# interface_dac_sma_feedback_3PS_LM317_par.net
KiCad netlist of a schematic drawn in EAGLE
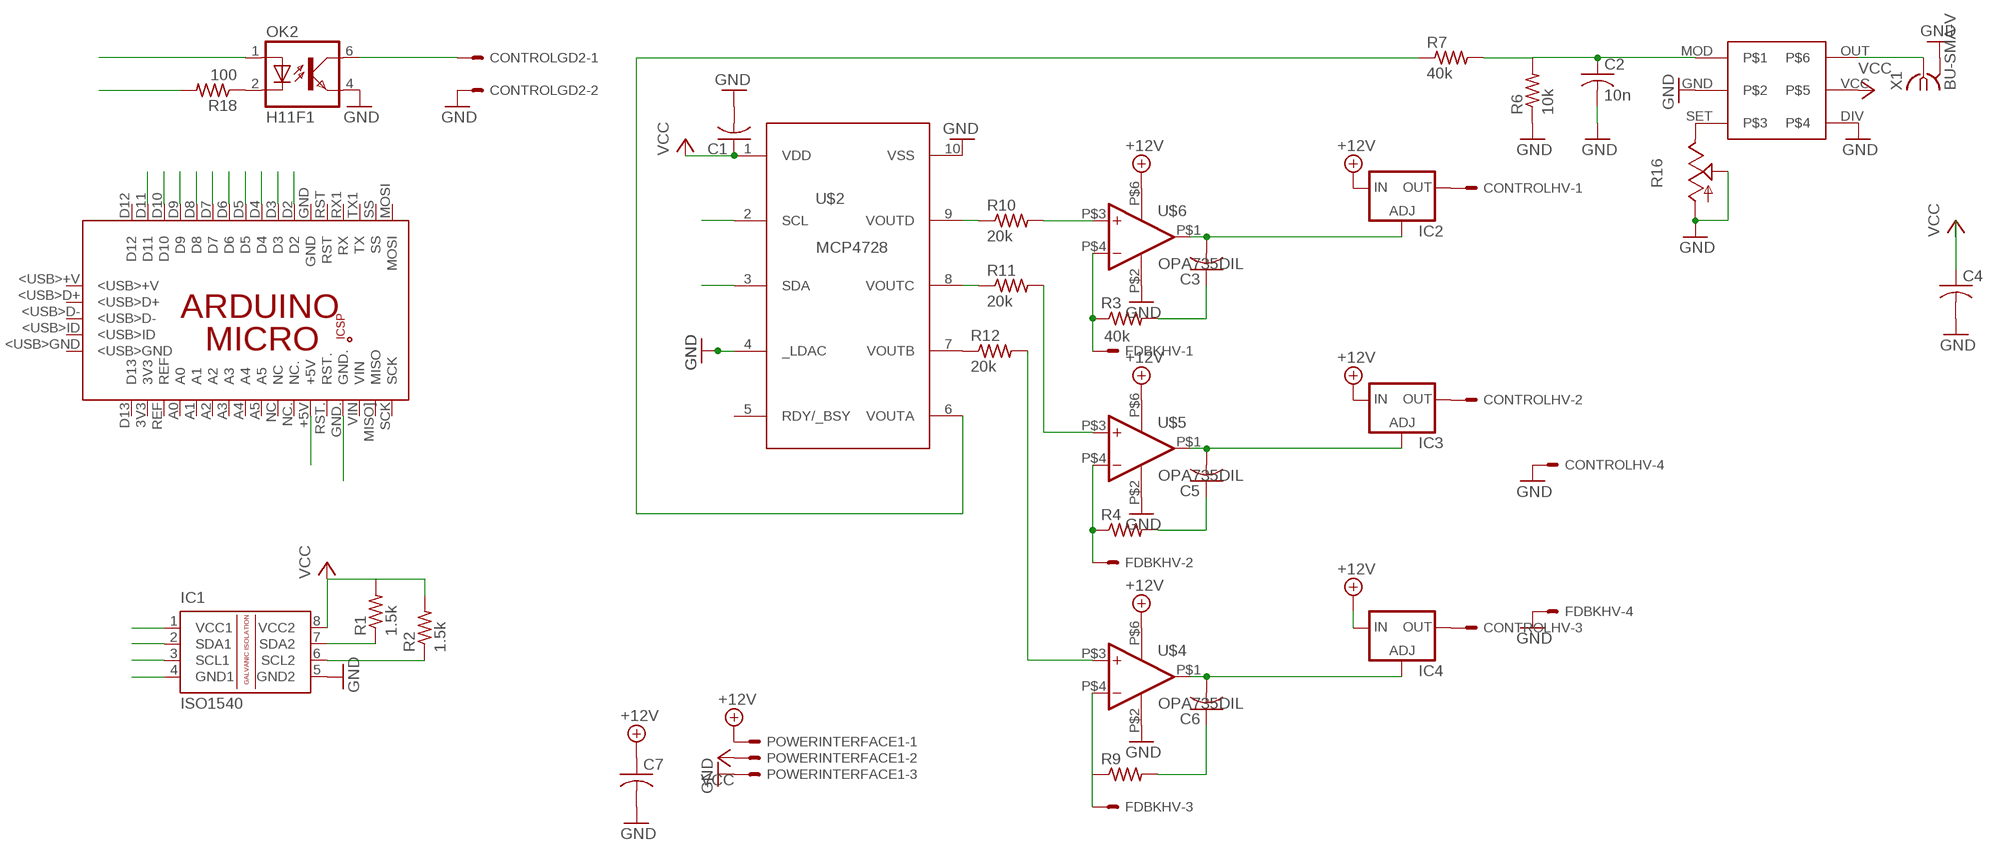
[diagram p0: schematic, sheet 1]

(export (version "E")
  (design (tool "Eeschema 10.0.6"))
  (components
    (comp (ref "C1")
      (value "C-US050-050X075")
      (footprint "eagle-import:C050-050X075")
      (libsource (lib "eagle-import") (part "C-US050-050X075"))
    )
    (comp (ref "C2")
      (value "10n")
      (footprint "eagle-import:C050-024X044")
      (libsource (lib "eagle-import") (part "resistor_C-US050-024X044"))
    )
    (comp (ref "C3")
      (value "C-US050-024X044")
      (footprint "eagle-import:C050-024X044")
      (libsource (lib "eagle-import") (part "resistor_C-US050-024X044"))
    )
    (comp (ref "C4")
      (value "C-US075-063X106")
      (footprint "eagle-import:C075-063X106")
      (libsource (lib "eagle-import") (part "resistor_C-US075-063X106"))
    )
    (comp (ref "C5")
      (value "C-US050-024X044")
      (footprint "eagle-import:C050-024X044")
      (libsource (lib "eagle-import") (part "resistor_C-US050-024X044"))
    )
    (comp (ref "C6")
      (value "C-US050-024X044")
      (footprint "eagle-import:C050-024X044")
      (libsource (lib "eagle-import") (part "resistor_C-US050-024X044"))
    )
    (comp (ref "C7")
      (value "C-US050-050X075")
      (footprint "eagle-import:C050-050X075")
      (libsource (lib "eagle-import") (part "resistor_C-US050-050X075"))
    )
    (comp (ref "CONTROLGD2")
      (value "KK-156-2")
      (footprint "eagle-import:KK-156-2")
      (libsource (lib "eagle-import") (part "KK-156-2"))
    )
    (comp (ref "CONTROLHV")
      (value "KK-156-4")
      (footprint "eagle-import:KK-156-4")
      (libsource (lib "eagle-import") (part "KK-156-4"))
    )
    (comp (ref "FDBKHV")
      (value "40k")
      (footprint "eagle-import:KK-156-4")
      (libsource (lib "eagle-import") (part "KK-156-4"))
    )
    (comp (ref "IC1")
      (value "ISO1540")
      (footprint "eagle-import:DIL08")
      (libsource (lib "eagle-import") (part "ISO1540"))
    )
    (comp (ref "IC2")
      (value "LM317TS")
      (footprint "eagle-import:317TS")
      (libsource (lib "eagle-import") (part "LM317TS"))
    )
    (comp (ref "IC3")
      (value "LM317TS")
      (footprint "eagle-import:317TS")
      (libsource (lib "eagle-import") (part "LM317TS"))
    )
    (comp (ref "IC4")
      (value "LM317TS")
      (footprint "eagle-import:317TS")
      (libsource (lib "eagle-import") (part "LM317TS"))
    )
    (comp (ref "OK2")
      (value "H11F1")
      (footprint "eagle-import:DIL05")
      (libsource (lib "eagle-import") (part "H11F1"))
    )
    (comp (ref "PCB1")
      (value "ARDUINO_MICRO")
      (footprint "eagle-import:ARDUINO_MICRO")
      (libsource (lib "eagle-import") (part "ARDUINO_MICRO"))
    )
    (comp (ref "POWERINTERFACE1")
      (value "KK-156-3")
      (footprint "eagle-import:KK-156-3")
      (libsource (lib "eagle-import") (part "KK-156-3"))
    )
    (comp (ref "R1")
      (value "1.5k")
      (footprint "eagle-import:0207_12")
      (libsource (lib "eagle-import") (part "resistor_R-US_0207/12"))
    )
    (comp (ref "R2")
      (value "1.5k")
      (footprint "eagle-import:0207_12")
      (libsource (lib "eagle-import") (part "resistor_R-US_0207/12"))
    )
    (comp (ref "R3")
      (value "R-US_0207/12")
      (footprint "eagle-import:0207_12")
      (libsource (lib "eagle-import") (part "resistor_R-US_0207/12"))
    )
    (comp (ref "R4")
      (value "R-US_0207/12")
      (footprint "eagle-import:0207_12")
      (libsource (lib "eagle-import") (part "resistor_R-US_0207/12"))
    )
    (comp (ref "R6")
      (value "10k")
      (footprint "eagle-import:0207_12")
      (libsource (lib "eagle-import") (part "resistor_R-US_0207/12"))
    )
    (comp (ref "R7")
      (value "40k")
      (footprint "eagle-import:0207_12")
      (libsource (lib "eagle-import") (part "resistor_R-US_0207/12"))
    )
    (comp (ref "R9")
      (value "R-US_0207/12")
      (footprint "eagle-import:0207_12")
      (libsource (lib "eagle-import") (part "resistor_R-US_0207/12"))
    )
    (comp (ref "R10")
      (value "20k")
      (footprint "eagle-import:0207_12")
      (libsource (lib "eagle-import") (part "resistor_R-US_0207/12"))
    )
    (comp (ref "R11")
      (value "20k")
      (footprint "eagle-import:0207_12")
      (libsource (lib "eagle-import") (part "resistor_R-US_0207/12"))
    )
    (comp (ref "R12")
      (value "20k")
      (footprint "eagle-import:0207_12")
      (libsource (lib "eagle-import") (part "resistor_R-US_0207/12"))
    )
    (comp (ref "R16")
      (value "TRIM_US-B90P")
      (footprint "eagle-import:SP19L")
      (libsource (lib "eagle-import") (part "TRIM_US-B90P"))
    )
    (comp (ref "R18")
      (value "100")
      (footprint "eagle-import:0207_12")
      (libsource (lib "eagle-import") (part "R-US_0207/12"))
    )
    (comp (ref "U$1")
      (value "LTC6992")
      (footprint "eagle-import:DIL06")
      (libsource (lib "eagle-import") (part "LTC6992"))
    )
    (comp (ref "U$2")
      (value "MCP4728DIL")
      (footprint "eagle-import:DIL10")
      (libsource (lib "eagle-import") (part "MCP4728DIL"))
    )
    (comp (ref "U$4")
      (value "OPA735DIL")
      (footprint "eagle-import:DIL6")
      (libsource (lib "eagle-import") (part "OPA735DIL"))
    )
    (comp (ref "U$5")
      (value "OPA735DIL")
      (footprint "eagle-import:DIL6")
      (libsource (lib "eagle-import") (part "OPA735DIL"))
    )
    (comp (ref "U$6")
      (value "OPA735DIL")
      (footprint "eagle-import:DIL6")
      (libsource (lib "eagle-import") (part "OPA735DIL"))
    )
    (comp (ref "X1")
      (value "BU-SMA-V")
      (footprint "eagle-import:BU-SMA-V")
      (libsource (lib "eagle-import") (part "BU-SMA-V"))
    )
  )
  (nets
    (net (code "1") (name "+12V") (class "Default")
      (node (ref "C7") (pin "1") (pinfunction "1_1") (pintype "passive"))
      (node (ref "IC2") (pin "3") (pinfunction "IN_3") (pintype "input"))
      (node (ref "IC3") (pin "3") (pinfunction "IN_3") (pintype "input"))
      (node (ref "IC4") (pin "3") (pinfunction "IN_3") (pintype "input"))
      (node (ref "POWERINTERFACE1") (pin "1") (pinfunction "S_1") (pintype "passive"))
      (node (ref "U$4") (pin "P$6") (pinfunction "V+_P$6") (pintype "power_in"))
      (node (ref "U$5") (pin "P$6") (pinfunction "V+_P$6") (pintype "power_in"))
      (node (ref "U$6") (pin "P$6") (pinfunction "V+_P$6") (pintype "power_in"))
    )
    (net (code "2") (name "/A+5") (class "Default")
      (node (ref "IC1") (pin "1") (pinfunction "VCC1_1") (pintype "input"))
      (node (ref "PCB1") (pin "+5V") (pinfunction "+5V_+5V") (pintype "bidirectional"))
    )
    (net (code "3") (name "/AGND") (class "Default")
      (node (ref "IC1") (pin "4") (pinfunction "GND1_4") (pintype "input"))
      (node (ref "PCB1") (pin "GND.") (pinfunction "GND._GND.") (pintype "bidirectional"))
      (node (ref "R18") (pin "2") (pinfunction "2_2") (pintype "passive"))
    )
    (net (code "4") (name "/N$2") (class "Default")
      (node (ref "C2") (pin "1") (pinfunction "1_1") (pintype "passive"))
      (node (ref "R6") (pin "2") (pinfunction "2_2") (pintype "passive"))
      (node (ref "R7") (pin "2") (pinfunction "2_2") (pintype "passive"))
      (node (ref "U$1") (pin "MOD") (pinfunction "P$1_MOD") (pintype "bidirectional"))
    )
    (net (code "5") (name "/PWM9") (class "Default")
      (node (ref "OK2") (pin "1") (pinfunction "A_1") (pintype "passive"))
      (node (ref "PCB1") (pin "D9") (pinfunction "D9_D9") (pintype "bidirectional"))
    )
    (net (code "6") (name "/SCL") (class "Default")
      (node (ref "IC1") (pin "3") (pinfunction "SCL1_3") (pintype "input"))
      (node (ref "PCB1") (pin "D3") (pinfunction "D3_D3") (pintype "bidirectional"))
    )
    (net (code "7") (name "/SCL_OUT") (class "Default")
      (node (ref "IC1") (pin "6") (pinfunction "SCL2_6") (pintype "input"))
      (node (ref "R2") (pin "1") (pinfunction "1_1") (pintype "passive"))
      (node (ref "U$2") (pin "2") (pinfunction "SCL_2") (pintype "bidirectional"))
    )
    (net (code "8") (name "/SDA") (class "Default")
      (node (ref "IC1") (pin "2") (pinfunction "SDA1_2") (pintype "input"))
      (node (ref "PCB1") (pin "D2") (pinfunction "D2_D2") (pintype "bidirectional"))
    )
    (net (code "9") (name "/SDA_OUT") (class "Default")
      (node (ref "IC1") (pin "7") (pinfunction "SDA2_7") (pintype "input"))
      (node (ref "R1") (pin "1") (pinfunction "1_1") (pintype "passive"))
      (node (ref "U$2") (pin "3") (pinfunction "SDA_3") (pintype "bidirectional"))
    )
    (net (code "10") (name "GND") (class "Default")
      (node (ref "C1") (pin "2") (pinfunction "2_2") (pintype "passive"))
      (node (ref "C2") (pin "2") (pinfunction "2_2") (pintype "passive"))
      (node (ref "C4") (pin "2") (pinfunction "2_2") (pintype "passive"))
      (node (ref "C7") (pin "2") (pinfunction "2_2") (pintype "passive"))
      (node (ref "CONTROLGD2") (pin "2") (pinfunction "S_2") (pintype "passive"))
      (node (ref "CONTROLHV") (pin "4") (pinfunction "S_4") (pintype "passive"))
      (node (ref "FDBKHV") (pin "4") (pinfunction "S_4") (pintype "passive"))
      (node (ref "IC1") (pin "5") (pinfunction "GND2_5") (pintype "input"))
      (node (ref "OK2") (pin "4") (pinfunction "EMIT_4") (pintype "passive"))
      (node (ref "POWERINTERFACE1") (pin "3") (pinfunction "S_3") (pintype "passive"))
      (node (ref "R16") (pin "A") (pinfunction "A_A") (pintype "passive"))
      (node (ref "R16") (pin "S") (pinfunction "S_S") (pintype "passive"))
      (node (ref "R6") (pin "1") (pinfunction "1_1") (pintype "passive"))
      (node (ref "U$1") (pin "DIV") (pinfunction "P$4_DIV") (pintype "bidirectional"))
      (node (ref "U$1") (pin "GND") (pinfunction "P$2_GND") (pintype "bidirectional"))
      (node (ref "U$2") (pin "10") (pinfunction "VSS_10") (pintype "bidirectional"))
      (node (ref "U$2") (pin "4") (pinfunction "_LDAC_4") (pintype "bidirectional"))
      (node (ref "U$4") (pin "P$2") (pinfunction "V-_P$2") (pintype "power_in"))
      (node (ref "U$5") (pin "P$2") (pinfunction "V-_P$2") (pintype "power_in"))
      (node (ref "U$6") (pin "P$2") (pinfunction "V-_P$2") (pintype "power_in"))
      (node (ref "X1") (pin "2") (pinfunction "2_2") (pintype "passive"))
      (node (ref "X1") (pin "3") (pinfunction "2_3") (pintype "passive"))
      (node (ref "X1") (pin "4") (pinfunction "2_4") (pintype "passive"))
      (node (ref "X1") (pin "5") (pinfunction "2_5") (pintype "passive"))
    )
    (net (code "11") (name "Net-(C3-Pad1)") (class "Default")
      (node (ref "C3") (pin "1") (pinfunction "1_1") (pintype "passive"))
      (node (ref "R3") (pin "2") (pinfunction "2_2") (pintype "passive"))
    )
    (net (code "12") (name "Net-(C5-Pad1)") (class "Default")
      (node (ref "C5") (pin "1") (pinfunction "1_1") (pintype "passive"))
      (node (ref "R4") (pin "2") (pinfunction "2_2") (pintype "passive"))
    )
    (net (code "13") (name "Net-(C6-Pad1)") (class "Default")
      (node (ref "C6") (pin "1") (pinfunction "1_1") (pintype "passive"))
      (node (ref "R9") (pin "2") (pinfunction "2_2") (pintype "passive"))
    )
    (net (code "14") (name "Net-(CONTROLGD2A-S)") (class "Default")
      (node (ref "CONTROLGD2") (pin "1") (pinfunction "S_1") (pintype "passive"))
      (node (ref "OK2") (pin "6") (pinfunction "COL_6") (pintype "passive"))
    )
    (net (code "15") (name "Net-(CONTROLHVA-S)") (class "Default")
      (node (ref "CONTROLHV") (pin "1") (pinfunction "S_1") (pintype "passive"))
      (node (ref "IC2") (pin "2") (pinfunction "OUT_2") (pintype "passive"))
    )
    (net (code "16") (name "Net-(CONTROLHVB-S)") (class "Default")
      (node (ref "CONTROLHV") (pin "2") (pinfunction "S_2") (pintype "passive"))
      (node (ref "IC3") (pin "2") (pinfunction "OUT_2") (pintype "passive"))
    )
    (net (code "17") (name "Net-(CONTROLHVC-S)") (class "Default")
      (node (ref "CONTROLHV") (pin "3") (pinfunction "S_3") (pintype "passive"))
      (node (ref "IC4") (pin "2") (pinfunction "OUT_2") (pintype "passive"))
    )
    (net (code "18") (name "Net-(FDBKHVA-S)") (class "Default")
      (node (ref "FDBKHV") (pin "1") (pinfunction "S_1") (pintype "passive"))
      (node (ref "R3") (pin "1") (pinfunction "1_1") (pintype "passive"))
      (node (ref "U$6") (pin "P$4") (pinfunction "-IN_P$4") (pintype "input"))
    )
    (net (code "19") (name "Net-(FDBKHVB-S)") (class "Default")
      (node (ref "FDBKHV") (pin "2") (pinfunction "S_2") (pintype "passive"))
      (node (ref "R4") (pin "1") (pinfunction "1_1") (pintype "passive"))
      (node (ref "U$5") (pin "P$4") (pinfunction "-IN_P$4") (pintype "input"))
    )
    (net (code "20") (name "Net-(FDBKHVC-S)") (class "Default")
      (node (ref "FDBKHV") (pin "3") (pinfunction "S_3") (pintype "passive"))
      (node (ref "R9") (pin "1") (pinfunction "1_1") (pintype "passive"))
      (node (ref "U$4") (pin "P$4") (pinfunction "-IN_P$4") (pintype "input"))
    )
    (net (code "21") (name "Net-(IC2-ADJ)") (class "Default")
      (node (ref "C3") (pin "2") (pinfunction "2_2") (pintype "passive"))
      (node (ref "IC2") (pin "1") (pinfunction "ADJ_1") (pintype "input"))
      (node (ref "U$6") (pin "P$1") (pinfunction "OUT_P$1") (pintype "output"))
    )
    (net (code "22") (name "Net-(IC3-ADJ)") (class "Default")
      (node (ref "C5") (pin "2") (pinfunction "2_2") (pintype "passive"))
      (node (ref "IC3") (pin "1") (pinfunction "ADJ_1") (pintype "input"))
      (node (ref "U$5") (pin "P$1") (pinfunction "OUT_P$1") (pintype "output"))
    )
    (net (code "23") (name "Net-(IC4-ADJ)") (class "Default")
      (node (ref "C6") (pin "2") (pinfunction "2_2") (pintype "passive"))
      (node (ref "IC4") (pin "1") (pinfunction "ADJ_1") (pintype "input"))
      (node (ref "U$4") (pin "P$1") (pinfunction "OUT_P$1") (pintype "output"))
    )
    (net (code "24") (name "Net-(OK2-C)") (class "Default")
      (node (ref "OK2") (pin "2") (pinfunction "C_2") (pintype "passive"))
      (node (ref "R18") (pin "1") (pinfunction "1_1") (pintype "passive"))
    )
    (net (code "25") (name "Net-(U$1-P$3)") (class "Default")
      (node (ref "R16") (pin "E") (pinfunction "E_E") (pintype "passive"))
      (node (ref "U$1") (pin "SET") (pinfunction "P$3_SET") (pintype "bidirectional"))
    )
    (net (code "26") (name "Net-(U$1-P$6)") (class "Default")
      (node (ref "U$1") (pin "OUT") (pinfunction "P$6_OUT") (pintype "bidirectional"))
      (node (ref "X1") (pin "1") (pinfunction "1_1") (pintype "passive"))
    )
    (net (code "27") (name "Net-(U$2-VOUTA)") (class "Default")
      (node (ref "R7") (pin "1") (pinfunction "1_1") (pintype "passive"))
      (node (ref "U$2") (pin "6") (pinfunction "VOUTA_6") (pintype "bidirectional"))
    )
    (net (code "28") (name "Net-(U$2-VOUTB)") (class "Default")
      (node (ref "R12") (pin "1") (pinfunction "1_1") (pintype "passive"))
      (node (ref "U$2") (pin "7") (pinfunction "VOUTB_7") (pintype "bidirectional"))
    )
    (net (code "29") (name "Net-(U$2-VOUTC)") (class "Default")
      (node (ref "R11") (pin "1") (pinfunction "1_1") (pintype "passive"))
      (node (ref "U$2") (pin "8") (pinfunction "VOUTC_8") (pintype "bidirectional"))
    )
    (net (code "30") (name "Net-(U$2-VOUTD)") (class "Default")
      (node (ref "R10") (pin "1") (pinfunction "1_1") (pintype "passive"))
      (node (ref "U$2") (pin "9") (pinfunction "VOUTD_9") (pintype "bidirectional"))
    )
    (net (code "31") (name "Net-(U$4-+IN)") (class "Default")
      (node (ref "R12") (pin "2") (pinfunction "2_2") (pintype "passive"))
      (node (ref "U$4") (pin "P$3") (pinfunction "+IN_P$3") (pintype "input"))
    )
    (net (code "32") (name "Net-(U$5-+IN)") (class "Default")
      (node (ref "R11") (pin "2") (pinfunction "2_2") (pintype "passive"))
      (node (ref "U$5") (pin "P$3") (pinfunction "+IN_P$3") (pintype "input"))
    )
    (net (code "33") (name "Net-(U$6-+IN)") (class "Default")
      (node (ref "R10") (pin "2") (pinfunction "2_2") (pintype "passive"))
      (node (ref "U$6") (pin "P$3") (pinfunction "+IN_P$3") (pintype "input"))
    )
    (net (code "34") (name "VCC") (class "Default")
      (node (ref "C1") (pin "1") (pinfunction "1_1") (pintype "passive"))
      (node (ref "C4") (pin "1") (pinfunction "1_1") (pintype "passive"))
      (node (ref "IC1") (pin "8") (pinfunction "VCC2_8") (pintype "input"))
      (node (ref "POWERINTERFACE1") (pin "2") (pinfunction "S_2") (pintype "passive"))
      (node (ref "R1") (pin "2") (pinfunction "2_2") (pintype "passive"))
      (node (ref "R2") (pin "2") (pinfunction "2_2") (pintype "passive"))
      (node (ref "U$1") (pin "VCC") (pinfunction "P$5_VCC") (pintype "bidirectional"))
      (node (ref "U$2") (pin "1") (pinfunction "VDD_1") (pintype "bidirectional"))
    )
    (net (code "35") (name "unconnected-(PCB1-MISO-PadMISO])") (class "Default")
      (node (ref "PCB1") (pin "MISO]") (pinfunction "MISO_MISO]") (pintype "bidirectional"))
    )
    (net (code "36") (name "unconnected-(PCB1-Pad3V3)") (class "Default")
      (node (ref "PCB1") (pin "3V3") (pinfunction "3V3_3V3") (pintype "bidirectional"))
    )
    (net (code "37") (name "unconnected-(PCB1-Pad5V)") (class "Default")
      (node (ref "PCB1") (pin "5V") (pinfunction "5V_5V") (pintype "bidirectional"))
    )
    (net (code "38") (name "unconnected-(PCB1-Pad<USB>+V)") (class "Default")
      (node (ref "PCB1") (pin "<USB>+V") (pinfunction "<USB>+V_<USB>+V") (pintype "bidirectional"))
    )
    (net (code "39") (name "unconnected-(PCB1-Pad<USB>D+)") (class "Default")
      (node (ref "PCB1") (pin "<USB>D+") (pinfunction "<USB>D+_<USB>D+") (pintype "bidirectional"))
    )
    (net (code "40") (name "unconnected-(PCB1-Pad<USB>D-)") (class "Default")
      (node (ref "PCB1") (pin "<USB>D-") (pinfunction "<USB>D-_<USB>D-") (pintype "bidirectional"))
    )
    (net (code "41") (name "unconnected-(PCB1-Pad<USB>GND)") (class "Default")
      (node (ref "PCB1") (pin "<USB>GND") (pinfunction "<USB>GND_<USB>GND") (pintype "bidirectional"))
    )
    (net (code "42") (name "unconnected-(PCB1-Pad<USB>ID)") (class "Default")
      (node (ref "PCB1") (pin "<USB>ID") (pinfunction "<USB>ID_<USB>ID") (pintype "bidirectional"))
    )
    (net (code "43") (name "unconnected-(PCB1-PadA0)") (class "Default")
      (node (ref "PCB1") (pin "A0") (pinfunction "A0_A0") (pintype "bidirectional"))
    )
    (net (code "44") (name "unconnected-(PCB1-PadA1)") (class "Default")
      (node (ref "PCB1") (pin "A1") (pinfunction "A1_A1") (pintype "bidirectional"))
    )
    (net (code "45") (name "unconnected-(PCB1-PadA2)") (class "Default")
      (node (ref "PCB1") (pin "A2") (pinfunction "A2_A2") (pintype "bidirectional"))
    )
    (net (code "46") (name "unconnected-(PCB1-PadA3)") (class "Default")
      (node (ref "PCB1") (pin "A3") (pinfunction "A3_A3") (pintype "bidirectional"))
    )
    (net (code "47") (name "unconnected-(PCB1-PadA4)") (class "Default")
      (node (ref "PCB1") (pin "A4") (pinfunction "A4_A4") (pintype "bidirectional"))
    )
    (net (code "48") (name "unconnected-(PCB1-PadA5)") (class "Default")
      (node (ref "PCB1") (pin "A5") (pinfunction "A5_A5") (pintype "bidirectional"))
    )
    (net (code "49") (name "unconnected-(PCB1-PadD4)") (class "Default")
      (node (ref "PCB1") (pin "D4") (pinfunction "D4_D4") (pintype "bidirectional"))
    )
    (net (code "50") (name "unconnected-(PCB1-PadD5)") (class "Default")
      (node (ref "PCB1") (pin "D5") (pinfunction "D5_D5") (pintype "bidirectional"))
    )
    (net (code "51") (name "unconnected-(PCB1-PadD6)") (class "Default")
      (node (ref "PCB1") (pin "D6") (pinfunction "D6_D6") (pintype "bidirectional"))
    )
    (net (code "52") (name "unconnected-(PCB1-PadD7)") (class "Default")
      (node (ref "PCB1") (pin "D7") (pinfunction "D7_D7") (pintype "bidirectional"))
    )
    (net (code "53") (name "unconnected-(PCB1-PadD8)") (class "Default")
      (node (ref "PCB1") (pin "D8") (pinfunction "D8_D8") (pintype "bidirectional"))
    )
    (net (code "54") (name "unconnected-(PCB1-PadD10)") (class "Default")
      (node (ref "PCB1") (pin "D10") (pinfunction "D10_D10") (pintype "bidirectional"))
    )
    (net (code "55") (name "unconnected-(PCB1-PadD11)") (class "Default")
      (node (ref "PCB1") (pin "D11") (pinfunction "D11_D11") (pintype "bidirectional"))
    )
    (net (code "56") (name "unconnected-(PCB1-PadD12)") (class "Default")
      (node (ref "PCB1") (pin "D12") (pinfunction "D12_D12") (pintype "bidirectional"))
    )
    (net (code "57") (name "unconnected-(PCB1-PadD13)") (class "Default")
      (node (ref "PCB1") (pin "D13") (pinfunction "D13_D13") (pintype "bidirectional"))
    )
    (net (code "58") (name "unconnected-(PCB1-PadGND)") (class "Default")
      (node (ref "PCB1") (pin "GND") (pinfunction "GND_GND") (pintype "bidirectional"))
    )
    (net (code "59") (name "unconnected-(PCB1-PadGND_)") (class "Default")
      (node (ref "PCB1") (pin "GND_") (pinfunction "GND__GND_") (pintype "bidirectional"))
    )
    (net (code "60") (name "unconnected-(PCB1-PadMISO.)") (class "Default")
      (node (ref "PCB1") (pin "MISO.") (pinfunction "MISO._MISO.") (pintype "bidirectional"))
    )
    (net (code "61") (name "unconnected-(PCB1-PadMOSI)") (class "Default")
      (node (ref "PCB1") (pin "MOSI") (pinfunction "MOSI_MOSI") (pintype "bidirectional"))
    )
    (net (code "62") (name "unconnected-(PCB1-PadMOSI.)") (class "Default")
      (node (ref "PCB1") (pin "MOSI.") (pinfunction "MOSI._MOSI.") (pintype "bidirectional"))
    )
    (net (code "63") (name "unconnected-(PCB1-PadNC)") (class "Default")
      (node (ref "PCB1") (pin "NC") (pinfunction "NC_NC") (pintype "bidirectional"))
    )
    (net (code "64") (name "unconnected-(PCB1-PadNC.)") (class "Default")
      (node (ref "PCB1") (pin "NC.") (pinfunction "NC._NC.") (pintype "bidirectional"))
    )
    (net (code "65") (name "unconnected-(PCB1-PadREF)") (class "Default")
      (node (ref "PCB1") (pin "REF") (pinfunction "REF_REF") (pintype "bidirectional"))
    )
    (net (code "66") (name "unconnected-(PCB1-PadRESET..)") (class "Default")
      (node (ref "PCB1") (pin "RESET..") (pinfunction "RESET.._RESET..") (pintype "bidirectional"))
    )
    (net (code "67") (name "unconnected-(PCB1-PadRST)") (class "Default")
      (node (ref "PCB1") (pin "RST") (pinfunction "RST_RST") (pintype "bidirectional"))
    )
    (net (code "68") (name "unconnected-(PCB1-PadRST.)") (class "Default")
      (node (ref "PCB1") (pin "RST.") (pinfunction "RST._RST.") (pintype "bidirectional"))
    )
    (net (code "69") (name "unconnected-(PCB1-PadSCK)") (class "Default")
      (node (ref "PCB1") (pin "SCK") (pinfunction "SCK_SCK") (pintype "bidirectional"))
    )
    (net (code "70") (name "unconnected-(PCB1-PadSCK.)") (class "Default")
      (node (ref "PCB1") (pin "SCK.") (pinfunction "SCK._SCK.") (pintype "bidirectional"))
    )
    (net (code "71") (name "unconnected-(PCB1-PadSS)") (class "Default")
      (node (ref "PCB1") (pin "SS") (pinfunction "SS_SS") (pintype "bidirectional"))
    )
    (net (code "72") (name "unconnected-(PCB1-PadVIN)") (class "Default")
      (node (ref "PCB1") (pin "VIN") (pinfunction "VIN_VIN") (pintype "bidirectional"))
    )
    (net (code "73") (name "unconnected-(PCB1-RX-PadRX1)") (class "Default")
      (node (ref "PCB1") (pin "RX1") (pinfunction "RX_RX1") (pintype "bidirectional"))
    )
    (net (code "74") (name "unconnected-(PCB1-TX-PadTX1)") (class "Default")
      (node (ref "PCB1") (pin "TX1") (pinfunction "TX_TX1") (pintype "bidirectional"))
    )
    (net (code "75") (name "unconnected-(U$2-RDY{slash}_BSY-Pad5)") (class "Default")
      (node (ref "U$2") (pin "5") (pinfunction "RDY/_BSY_5") (pintype "bidirectional"))
    )
  )
)
